# handmouse.net
KiCad netlist of a schematic drawn in Altium Designer
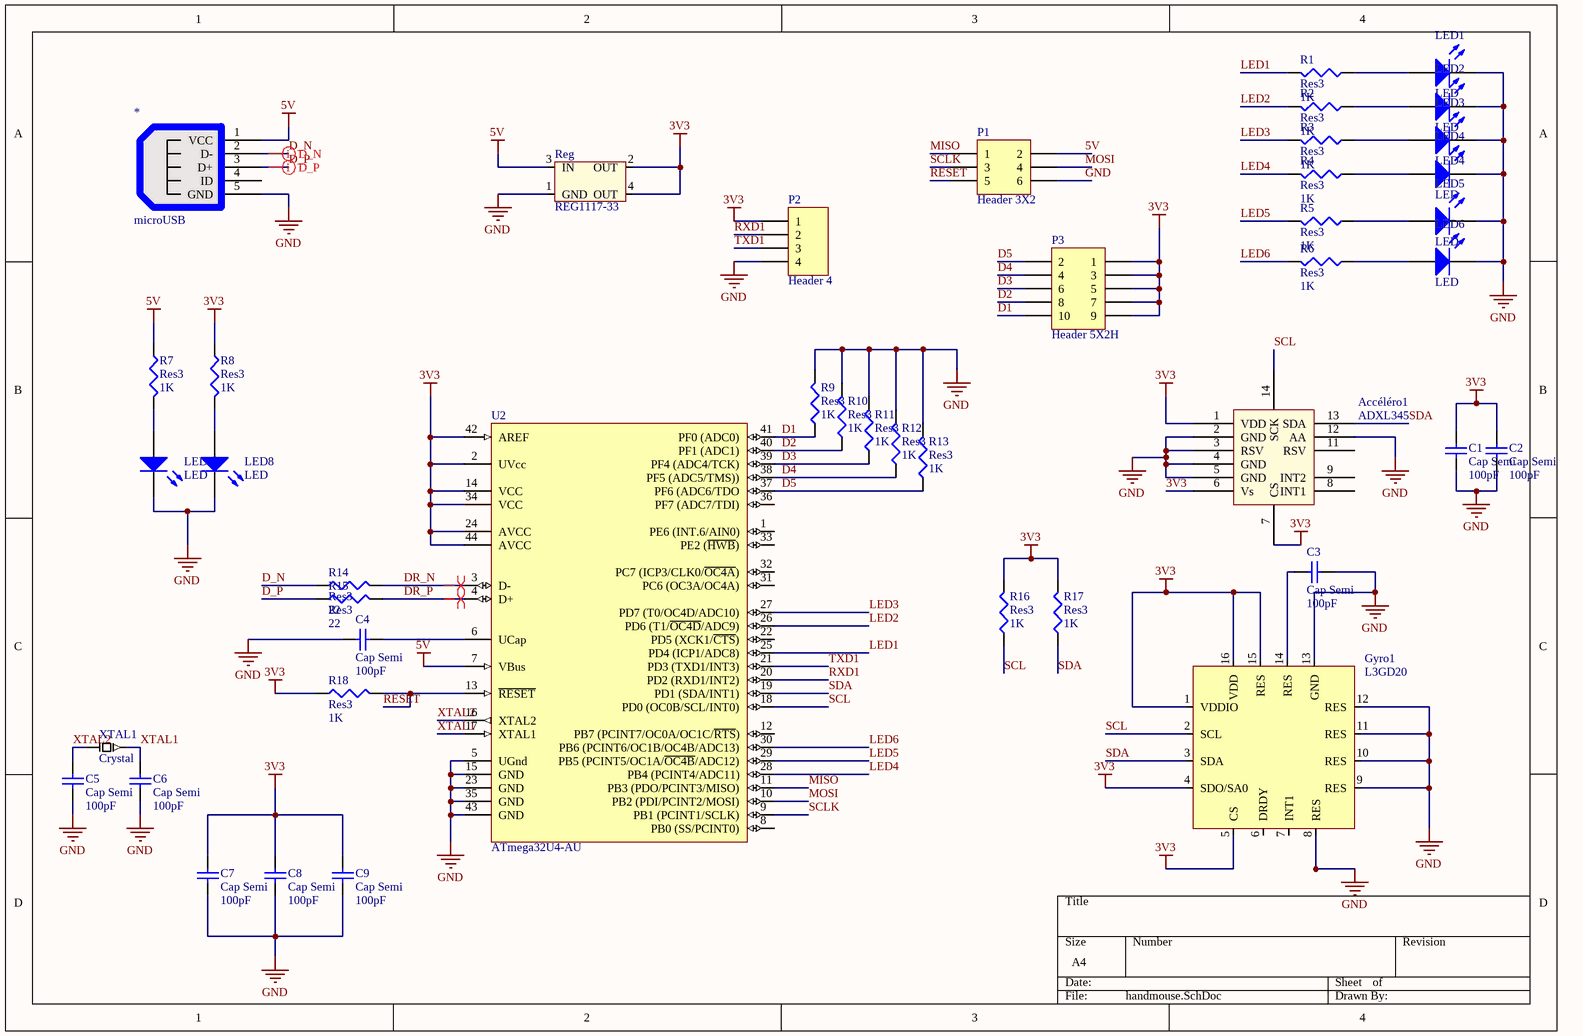
[diagram p0: handmouse.SchDoc]

(export (version "E")
  (design (tool "Eeschema 10.0.6"))
  (components
    (comp (ref "*") (value "microUSB") (footprint "microUSB") (libsource (lib "Schlib1") (part "microUSB")))
    (comp (ref "Accéléro1")
      (value "ADXL345")
      (footprint "PcbLib1:LGA-14")
      (libsource (lib "Schlib1") (part "ADXL345"))
    )
    (comp (ref "C1")
      (value "Cap Semi")
      (footprint "1608[0603]")
      (description "Capacitor (Semiconductor SIM Model)")
      (fields (field (name "ALTIUM_VALUE") "100pF") (field (name "PUBLISHER") "Altium Limited"))
      (libsource (lib "Miscellaneous Devices") (part "Cap Semi"))
    )
    (comp (ref "C2")
      (value "Cap Semi")
      (footprint "1608[0603]")
      (description "Capacitor (Semiconductor SIM Model)")
      (fields (field (name "ALTIUM_VALUE") "100pF") (field (name "PUBLISHER") "Altium Limited"))
      (libsource (lib "Miscellaneous Devices") (part "Cap Semi"))
    )
    (comp (ref "C3")
      (value "Cap Semi")
      (footprint "1608[0603]")
      (description "Capacitor (Semiconductor SIM Model)")
      (fields (field (name "ALTIUM_VALUE") "100pF") (field (name "PUBLISHER") "Altium Limited"))
      (libsource (lib "Miscellaneous Devices") (part "Cap Semi"))
    )
    (comp (ref "C4")
      (value "Cap Semi")
      (footprint "1608[0603]")
      (description "Capacitor (Semiconductor SIM Model)")
      (fields (field (name "ALTIUM_VALUE") "100pF") (field (name "PUBLISHER") "Altium Limited"))
      (libsource (lib "Miscellaneous Devices") (part "Cap Semi"))
    )
    (comp (ref "C5")
      (value "Cap Semi")
      (footprint "1608[0603]")
      (description "Capacitor (Semiconductor SIM Model)")
      (fields (field (name "ALTIUM_VALUE") "100pF") (field (name "PUBLISHER") "Altium Limited"))
      (libsource (lib "Miscellaneous Devices") (part "Cap Semi"))
    )
    (comp (ref "C6")
      (value "Cap Semi")
      (footprint "1608[0603]")
      (description "Capacitor (Semiconductor SIM Model)")
      (fields (field (name "ALTIUM_VALUE") "100pF") (field (name "PUBLISHER") "Altium Limited"))
      (libsource (lib "Miscellaneous Devices") (part "Cap Semi"))
    )
    (comp (ref "C7")
      (value "Cap Semi")
      (footprint "1608[0603]")
      (description "Capacitor (Semiconductor SIM Model)")
      (fields (field (name "ALTIUM_VALUE") "100pF") (field (name "PUBLISHER") "Altium Limited"))
      (libsource (lib "Miscellaneous Devices") (part "Cap Semi"))
    )
    (comp (ref "C8")
      (value "Cap Semi")
      (footprint "1608[0603]")
      (description "Capacitor (Semiconductor SIM Model)")
      (fields (field (name "ALTIUM_VALUE") "100pF") (field (name "PUBLISHER") "Altium Limited"))
      (libsource (lib "Miscellaneous Devices") (part "Cap Semi"))
    )
    (comp (ref "C9")
      (value "Cap Semi")
      (footprint "1608[0603]")
      (description "Capacitor (Semiconductor SIM Model)")
      (fields (field (name "ALTIUM_VALUE") "100pF") (field (name "PUBLISHER") "Altium Limited"))
      (libsource (lib "Miscellaneous Devices") (part "Cap Semi"))
    )
    (comp (ref "Gyro1")
      (value "L3GD20")
      (footprint "PcbLib1:QFN16")
      (libsource (lib "Schlib1") (part "L3GD20"))
    )
    (comp (ref "LED1") (value "LED") (footprint "LED 0603") (libsource (lib "Schlib1") (part "LED")))
    (comp (ref "LED2") (value "LED") (footprint "LED 0603") (libsource (lib "Schlib1") (part "LED")))
    (comp (ref "LED3") (value "LED4") (footprint "LED 0603") (libsource (lib "Schlib1") (part "LED")))
    (comp (ref "LED4") (value "LED") (footprint "LED 0603") (libsource (lib "Schlib1") (part "LED")))
    (comp (ref "LED5") (value "LED") (footprint "LED 0603") (libsource (lib "Schlib1") (part "LED")))
    (comp (ref "LED6") (value "LED") (footprint "LED 0603") (libsource (lib "Schlib1") (part "LED")))
    (comp (ref "LED7") (value "LED") (footprint "LED 0603") (libsource (lib "Schlib1") (part "LED")))
    (comp (ref "LED8") (value "LED") (footprint "LED 0603") (libsource (lib "Schlib1") (part "LED")))
    (comp (ref "P1")
      (value "Header 3X2")
      (footprint "HDR2X3")
      (description "Header, 3-Pin, Dual row")
      (fields (field (name "PUBLISHER") "Altium Limited"))
      (libsource (lib "Miscellaneous Connectors") (part "Header 3X2"))
    )
    (comp (ref "P2")
      (value "Header 4")
      (footprint "HDR1X4")
      (description "Header, 4-Pin")
      (fields (field (name "PUBLISHER") "Altium Limited"))
      (libsource (lib "Miscellaneous Connectors") (part "Header 4"))
    )
    (comp (ref "P3")
      (value "Header 5X2H")
      (footprint "HDR2X5H")
      (description "Header, 5-Pin, Dual row, Right Angle")
      (fields (field (name "PUBLISHER") "Altium Limited"))
      (libsource (lib "Miscellaneous Connectors") (part "Header 5X2H"))
    )
    (comp (ref "R1")
      (value "Res3")
      (footprint "J1-0603")
      (description "Resistor")
      (fields (field (name "ALTIUM_VALUE") "1K") (field (name "PUBLISHER") "Altium Limited"))
      (libsource (lib "Miscellaneous Devices") (part "Res3"))
    )
    (comp (ref "R2")
      (value "Res3")
      (footprint "J1-0603")
      (description "Resistor")
      (fields (field (name "ALTIUM_VALUE") "1K") (field (name "PUBLISHER") "Altium Limited"))
      (libsource (lib "Miscellaneous Devices") (part "Res3"))
    )
    (comp (ref "R3")
      (value "Res3")
      (footprint "J1-0603")
      (description "Resistor")
      (fields (field (name "ALTIUM_VALUE") "1K") (field (name "PUBLISHER") "Altium Limited"))
      (libsource (lib "Miscellaneous Devices") (part "Res3"))
    )
    (comp (ref "R4")
      (value "Res3")
      (footprint "J1-0603")
      (description "Resistor")
      (fields (field (name "ALTIUM_VALUE") "1K") (field (name "PUBLISHER") "Altium Limited"))
      (libsource (lib "Miscellaneous Devices") (part "Res3"))
    )
    (comp (ref "R5")
      (value "Res3")
      (footprint "J1-0603")
      (description "Resistor")
      (fields (field (name "ALTIUM_VALUE") "1K") (field (name "PUBLISHER") "Altium Limited"))
      (libsource (lib "Miscellaneous Devices") (part "Res3"))
    )
    (comp (ref "R6")
      (value "Res3")
      (footprint "J1-0603")
      (description "Resistor")
      (fields (field (name "ALTIUM_VALUE") "1K") (field (name "PUBLISHER") "Altium Limited"))
      (libsource (lib "Miscellaneous Devices") (part "Res3"))
    )
    (comp (ref "R7")
      (value "Res3")
      (footprint "J1-0603")
      (description "Resistor")
      (fields (field (name "ALTIUM_VALUE") "1K") (field (name "PUBLISHER") "Altium Limited"))
      (libsource (lib "Miscellaneous Devices") (part "Res3"))
    )
    (comp (ref "R8")
      (value "Res3")
      (footprint "J1-0603")
      (description "Resistor")
      (fields (field (name "ALTIUM_VALUE") "1K") (field (name "PUBLISHER") "Altium Limited"))
      (libsource (lib "Miscellaneous Devices") (part "Res3"))
    )
    (comp (ref "R9")
      (value "Res3")
      (footprint "J1-0603")
      (description "Resistor")
      (fields (field (name "ALTIUM_VALUE") "1K") (field (name "PUBLISHER") "Altium Limited"))
      (libsource (lib "Miscellaneous Devices") (part "Res3"))
    )
    (comp (ref "R10")
      (value "Res3")
      (footprint "J1-0603")
      (description "Resistor")
      (fields (field (name "ALTIUM_VALUE") "1K") (field (name "PUBLISHER") "Altium Limited"))
      (libsource (lib "Miscellaneous Devices") (part "Res3"))
    )
    (comp (ref "R11")
      (value "Res3")
      (footprint "J1-0603")
      (description "Resistor")
      (fields (field (name "ALTIUM_VALUE") "1K") (field (name "PUBLISHER") "Altium Limited"))
      (libsource (lib "Miscellaneous Devices") (part "Res3"))
    )
    (comp (ref "R12")
      (value "Res3")
      (footprint "J1-0603")
      (description "Resistor")
      (fields (field (name "ALTIUM_VALUE") "1K") (field (name "PUBLISHER") "Altium Limited"))
      (libsource (lib "Miscellaneous Devices") (part "Res3"))
    )
    (comp (ref "R13")
      (value "Res3")
      (footprint "J1-0603")
      (description "Resistor")
      (fields (field (name "ALTIUM_VALUE") "1K") (field (name "PUBLISHER") "Altium Limited"))
      (libsource (lib "Miscellaneous Devices") (part "Res3"))
    )
    (comp (ref "R14")
      (value "Res3")
      (footprint "J1-0603")
      (description "Resistor")
      (fields (field (name "ALTIUM_VALUE") "22") (field (name "PUBLISHER") "Altium Limited"))
      (libsource (lib "Miscellaneous Devices") (part "Res3"))
    )
    (comp (ref "R15")
      (value "Res3")
      (footprint "J1-0603")
      (description "Resistor")
      (fields (field (name "ALTIUM_VALUE") "22") (field (name "PUBLISHER") "Altium Limited"))
      (libsource (lib "Miscellaneous Devices") (part "Res3"))
    )
    (comp (ref "R16")
      (value "Res3")
      (footprint "J1-0603")
      (description "Resistor")
      (fields (field (name "ALTIUM_VALUE") "1K") (field (name "PUBLISHER") "Altium Limited"))
      (libsource (lib "Miscellaneous Devices") (part "Res3"))
    )
    (comp (ref "R17")
      (value "Res3")
      (footprint "J1-0603")
      (description "Resistor")
      (fields (field (name "ALTIUM_VALUE") "1K") (field (name "PUBLISHER") "Altium Limited"))
      (libsource (lib "Miscellaneous Devices") (part "Res3"))
    )
    (comp (ref "R18")
      (value "Res3")
      (footprint "J1-0603")
      (description "Resistor")
      (fields (field (name "ALTIUM_VALUE") "1K") (field (name "PUBLISHER") "Altium Limited"))
      (libsource (lib "Miscellaneous Devices") (part "Res3"))
    )
    (comp (ref "Reg")
      (value "REG1117-33")
      (footprint "SOT-223")
      (libsource (lib "Schlib1") (part "REG1117-33"))
    )
    (comp (ref "U2")
      (value "ATmega32U4-AU")
      (footprint "44ML_N")
      (fields (field (name "PUBLISHER") "Altium Limited"))
      (libsource (lib "Atmel Microcontroller 8-Bit megaAVR") (part "ATmega32U4-AU"))
    )
    (comp (ref "XTAL1") (value "Crystal") (footprint "HC49-CMS") (libsource (lib "Schlib1") (part "Crystal")))
  )
  (nets
    (net (code "1") (name "/D1") (class "Default")
      (node (ref "P3") (pin "10") (pinfunction "10_10") (pintype "passive"))
      (node (ref "R9") (pin "1") (pinfunction "1_1") (pintype "passive"))
      (node (ref "U2") (pin "41") (pinfunction "PF0_(ADC0)_41") (pintype "bidirectional"))
    )
    (net (code "2") (name "/D2") (class "Default")
      (node (ref "P3") (pin "8") (pinfunction "8_8") (pintype "passive"))
      (node (ref "R10") (pin "1") (pinfunction "1_1") (pintype "passive"))
      (node (ref "U2") (pin "40") (pinfunction "PF1_(ADC1)_40") (pintype "bidirectional"))
    )
    (net (code "3") (name "/D3") (class "Default")
      (node (ref "P3") (pin "6") (pinfunction "6_6") (pintype "passive"))
      (node (ref "R11") (pin "1") (pinfunction "1_1") (pintype "passive"))
      (node (ref "U2") (pin "39") (pinfunction "PF4_(ADC4/TCK)_39") (pintype "bidirectional"))
    )
    (net (code "4") (name "/D4") (class "Default")
      (node (ref "P3") (pin "4") (pinfunction "4_4") (pintype "passive"))
      (node (ref "R12") (pin "1") (pinfunction "1_1") (pintype "passive"))
      (node (ref "U2") (pin "38") (pinfunction "PF5_(ADC5/TMS))_38") (pintype "bidirectional"))
    )
    (net (code "5") (name "/D5") (class "Default")
      (node (ref "P3") (pin "2") (pinfunction "2_2") (pintype "passive"))
      (node (ref "R13") (pin "1") (pinfunction "1_1") (pintype "passive"))
      (node (ref "U2") (pin "37") (pinfunction "PF6_(ADC6/TDO_37") (pintype "bidirectional"))
    )
    (net (code "6") (name "/DR_N") (class "Default")
      (node (ref "R14") (pin "2") (pinfunction "2_2") (pintype "passive"))
      (node (ref "U2") (pin "3") (pinfunction "D-_3") (pintype "bidirectional"))
    )
    (net (code "7") (name "/DR_P") (class "Default")
      (node (ref "R15") (pin "2") (pinfunction "2_2") (pintype "passive"))
      (node (ref "U2") (pin "4") (pinfunction "D+_4") (pintype "bidirectional"))
    )
    (net (code "8") (name "/D_N") (class "Default")
      (node (ref "*") (pin "2") (pinfunction "D-_2") (pintype "passive"))
      (node (ref "R14") (pin "1") (pinfunction "1_1") (pintype "passive"))
    )
    (net (code "9") (name "/D_P") (class "Default")
      (node (ref "*") (pin "3") (pinfunction "D+_3") (pintype "passive"))
      (node (ref "R15") (pin "1") (pinfunction "1_1") (pintype "passive"))
    )
    (net (code "10") (name "/LED1") (class "Default")
      (node (ref "R1") (pin "2") (pinfunction "2_2") (pintype "passive"))
      (node (ref "U2") (pin "25") (pinfunction "PD4_(ICP1/ADC8)_25") (pintype "bidirectional"))
    )
    (net (code "11") (name "/LED2") (class "Default")
      (node (ref "R2") (pin "2") (pinfunction "2_2") (pintype "passive"))
      (node (ref "U2") (pin "26") (pinfunction "PD6_(T1/~{OC4D}/ADC9)_26") (pintype "bidirectional"))
    )
    (net (code "12") (name "/LED3") (class "Default")
      (node (ref "R3") (pin "2") (pinfunction "2_2") (pintype "passive"))
      (node (ref "U2") (pin "27") (pinfunction "PD7_(T0/OC4D/ADC10)_27") (pintype "bidirectional"))
    )
    (net (code "13") (name "/LED4") (class "Default")
      (node (ref "R4") (pin "2") (pinfunction "2_2") (pintype "passive"))
      (node (ref "U2") (pin "28") (pinfunction "PB4_(PCINT4/ADC11)_28") (pintype "bidirectional"))
    )
    (net (code "14") (name "/LED5") (class "Default")
      (node (ref "R5") (pin "2") (pinfunction "2_2") (pintype "passive"))
      (node (ref "U2") (pin "29") (pinfunction "PB5_(PCINT5/OC1A/~{OC4B}/ADC12)_29") (pintype "bidirectional"))
    )
    (net (code "15") (name "/LED6") (class "Default")
      (node (ref "R6") (pin "2") (pinfunction "2_2") (pintype "passive"))
      (node (ref "U2") (pin "30") (pinfunction "PB6_(PCINT6/OC1B/OC4B/ADC13)_30") (pintype "bidirectional"))
    )
    (net (code "16") (name "/MISO") (class "Default")
      (node (ref "P1") (pin "1") (pinfunction "1_1") (pintype "passive"))
      (node (ref "U2") (pin "11") (pinfunction "PB3_(PDO/PCINT3/MISO)_11") (pintype "bidirectional"))
    )
    (net (code "17") (name "/MOSI") (class "Default")
      (node (ref "P1") (pin "4") (pinfunction "4_4") (pintype "passive"))
      (node (ref "U2") (pin "10") (pinfunction "PB2_(PDI/PCINT2/MOSI)_10") (pintype "bidirectional"))
    )
    (net (code "18") (name "/RESET") (class "Default")
      (node (ref "P1") (pin "5") (pinfunction "5_5") (pintype "passive"))
      (node (ref "R18") (pin "2") (pinfunction "2_2") (pintype "passive"))
      (node (ref "U2") (pin "13") (pinfunction "~{RESET}_13") (pintype "input"))
    )
    (net (code "19") (name "/RXD1") (class "Default")
      (node (ref "P2") (pin "2") (pinfunction "2_2") (pintype "passive"))
      (node (ref "U2") (pin "20") (pinfunction "PD2_(RXD1/INT2)_20") (pintype "bidirectional"))
    )
    (net (code "20") (name "/SCL") (class "Default")
      (node (ref "Accéléro1") (pin "14") (pinfunction "SCK_14") (pintype "passive"))
      (node (ref "Gyro1") (pin "2") (pinfunction "SCL_2") (pintype "passive"))
      (node (ref "R16") (pin "1") (pinfunction "1_1") (pintype "passive"))
      (node (ref "U2") (pin "18") (pinfunction "PD0_(OC0B/SCL/INT0)_18") (pintype "bidirectional"))
    )
    (net (code "21") (name "/SCLK") (class "Default")
      (node (ref "P1") (pin "3") (pinfunction "3_3") (pintype "passive"))
      (node (ref "U2") (pin "9") (pinfunction "PB1_(PCINT1/SCLK)_9") (pintype "bidirectional"))
    )
    (net (code "22") (name "/SDA") (class "Default")
      (node (ref "Accéléro1") (pin "13") (pinfunction "SDA_13") (pintype "passive"))
      (node (ref "Gyro1") (pin "3") (pinfunction "SDA_3") (pintype "passive"))
      (node (ref "R17") (pin "1") (pinfunction "1_1") (pintype "passive"))
      (node (ref "U2") (pin "19") (pinfunction "PD1_(SDA/INT1)_19") (pintype "bidirectional"))
    )
    (net (code "23") (name "/TXD1") (class "Default")
      (node (ref "P2") (pin "3") (pinfunction "3_3") (pintype "passive"))
      (node (ref "U2") (pin "21") (pinfunction "PD3_(TXD1/INT3)_21") (pintype "bidirectional"))
    )
    (net (code "24") (name "/XTAL1") (class "Default")
      (node (ref "C6") (pin "2") (pinfunction "2_2") (pintype "passive"))
      (node (ref "U2") (pin "17") (pinfunction "XTAL1_17") (pintype "input"))
      (node (ref "XTAL1") (pin "2") (pinfunction "2_2") (pintype "output"))
    )
    (net (code "25") (name "/XTAL2") (class "Default")
      (node (ref "C5") (pin "2") (pinfunction "2_2") (pintype "passive"))
      (node (ref "U2") (pin "16") (pinfunction "XTAL2_16") (pintype "output"))
      (node (ref "XTAL1") (pin "1") (pinfunction "1_1") (pintype "passive"))
    )
    (net (code "26") (name "3V3") (class "Default")
      (node (ref "Accéléro1") (pin "1") (pinfunction "VDD_1") (pintype "power_in"))
      (node (ref "Accéléro1") (pin "6") (pinfunction "Vs_6") (pintype "passive"))
      (node (ref "Accéléro1") (pin "7") (pinfunction "CS_7") (pintype "passive"))
      (node (ref "C1") (pin "2") (pinfunction "2_2") (pintype "passive"))
      (node (ref "C2") (pin "2") (pinfunction "2_2") (pintype "passive"))
      (node (ref "C7") (pin "2") (pinfunction "2_2") (pintype "passive"))
      (node (ref "C8") (pin "2") (pinfunction "2_2") (pintype "passive"))
      (node (ref "C9") (pin "2") (pinfunction "2_2") (pintype "passive"))
      (node (ref "Gyro1") (pin "1") (pinfunction "VDDIO_1") (pintype "power_in"))
      (node (ref "Gyro1") (pin "15") (pinfunction "RES_15") (pintype "passive"))
      (node (ref "Gyro1") (pin "16") (pinfunction "VDD_16") (pintype "power_in"))
      (node (ref "Gyro1") (pin "4") (pinfunction "SDO/SA0_4") (pintype "passive"))
      (node (ref "Gyro1") (pin "5") (pinfunction "CS_5") (pintype "passive"))
      (node (ref "P2") (pin "1") (pinfunction "1_1") (pintype "passive"))
      (node (ref "P3") (pin "1") (pinfunction "1_1") (pintype "passive"))
      (node (ref "P3") (pin "3") (pinfunction "3_3") (pintype "passive"))
      (node (ref "P3") (pin "5") (pinfunction "5_5") (pintype "passive"))
      (node (ref "P3") (pin "7") (pinfunction "7_7") (pintype "passive"))
      (node (ref "P3") (pin "9") (pinfunction "9_9") (pintype "passive"))
      (node (ref "R16") (pin "2") (pinfunction "2_2") (pintype "passive"))
      (node (ref "R17") (pin "2") (pinfunction "2_2") (pintype "passive"))
      (node (ref "R18") (pin "1") (pinfunction "1_1") (pintype "passive"))
      (node (ref "R8") (pin "1") (pinfunction "1_1") (pintype "passive"))
      (node (ref "Reg") (pin "2") (pinfunction "OUT_2") (pintype "passive"))
      (node (ref "Reg") (pin "4") (pinfunction "OUT_4") (pintype "passive"))
      (node (ref "U2") (pin "14") (pinfunction "VCC_14") (pintype "power_in"))
      (node (ref "U2") (pin "2") (pinfunction "UVcc_2") (pintype "power_in"))
      (node (ref "U2") (pin "24") (pinfunction "AVCC_24") (pintype "power_in"))
      (node (ref "U2") (pin "34") (pinfunction "VCC_34") (pintype "power_in"))
      (node (ref "U2") (pin "42") (pinfunction "AREF_42") (pintype "input"))
      (node (ref "U2") (pin "44") (pinfunction "AVCC_44") (pintype "power_in"))
    )
    (net (code "27") (name "5V") (class "Default")
      (node (ref "*") (pin "1") (pinfunction "VCC_1") (pintype "power_in"))
      (node (ref "P1") (pin "2") (pinfunction "2_2") (pintype "passive"))
      (node (ref "R7") (pin "1") (pinfunction "1_1") (pintype "passive"))
      (node (ref "Reg") (pin "3") (pinfunction "IN_3") (pintype "passive"))
      (node (ref "U2") (pin "7") (pinfunction "VBus_7") (pintype "input"))
    )
    (net (code "28") (name "GND") (class "Default")
      (node (ref "*") (pin "5") (pinfunction "GND_5") (pintype "passive"))
      (node (ref "Accéléro1") (pin "12") (pinfunction "AA_12") (pintype "passive"))
      (node (ref "Accéléro1") (pin "2") (pinfunction "GND_2") (pintype "power_in"))
      (node (ref "Accéléro1") (pin "3") (pinfunction "RSV_3") (pintype "passive"))
      (node (ref "Accéléro1") (pin "4") (pinfunction "GND_4") (pintype "power_in"))
      (node (ref "Accéléro1") (pin "5") (pinfunction "GND_5") (pintype "power_in"))
      (node (ref "C1") (pin "1") (pinfunction "1_1") (pintype "passive"))
      (node (ref "C2") (pin "1") (pinfunction "1_1") (pintype "passive"))
      (node (ref "C3") (pin "1") (pinfunction "1_1") (pintype "passive"))
      (node (ref "C4") (pin "2") (pinfunction "2_2") (pintype "passive"))
      (node (ref "C5") (pin "1") (pinfunction "1_1") (pintype "passive"))
      (node (ref "C6") (pin "1") (pinfunction "1_1") (pintype "passive"))
      (node (ref "C7") (pin "1") (pinfunction "1_1") (pintype "passive"))
      (node (ref "C8") (pin "1") (pinfunction "1_1") (pintype "passive"))
      (node (ref "C9") (pin "1") (pinfunction "1_1") (pintype "passive"))
      (node (ref "Gyro1") (pin "10") (pinfunction "RES_10") (pintype "passive"))
      (node (ref "Gyro1") (pin "11") (pinfunction "RES_11") (pintype "passive"))
      (node (ref "Gyro1") (pin "12") (pinfunction "RES_12") (pintype "passive"))
      (node (ref "Gyro1") (pin "13") (pinfunction "GND_13") (pintype "passive"))
      (node (ref "Gyro1") (pin "8") (pinfunction "RES_8") (pintype "passive"))
      (node (ref "Gyro1") (pin "9") (pinfunction "RES_9") (pintype "passive"))
      (node (ref "LED1") (pin "2") (pinfunction "K_2") (pintype "passive"))
      (node (ref "LED2") (pin "2") (pinfunction "K_2") (pintype "passive"))
      (node (ref "LED3") (pin "2") (pinfunction "K_2") (pintype "passive"))
      (node (ref "LED4") (pin "2") (pinfunction "K_2") (pintype "passive"))
      (node (ref "LED5") (pin "2") (pinfunction "K_2") (pintype "passive"))
      (node (ref "LED6") (pin "2") (pinfunction "K_2") (pintype "passive"))
      (node (ref "LED7") (pin "2") (pinfunction "K_2") (pintype "passive"))
      (node (ref "LED8") (pin "2") (pinfunction "K_2") (pintype "passive"))
      (node (ref "P1") (pin "6") (pinfunction "6_6") (pintype "passive"))
      (node (ref "P2") (pin "4") (pinfunction "4_4") (pintype "passive"))
      (node (ref "R10") (pin "2") (pinfunction "2_2") (pintype "passive"))
      (node (ref "R11") (pin "2") (pinfunction "2_2") (pintype "passive"))
      (node (ref "R12") (pin "2") (pinfunction "2_2") (pintype "passive"))
      (node (ref "R13") (pin "2") (pinfunction "2_2") (pintype "passive"))
      (node (ref "R9") (pin "2") (pinfunction "2_2") (pintype "passive"))
      (node (ref "Reg") (pin "1") (pinfunction "GND_1") (pintype "passive"))
      (node (ref "U2") (pin "15") (pinfunction "GND_15") (pintype "power_in"))
      (node (ref "U2") (pin "23") (pinfunction "GND_23") (pintype "power_in"))
      (node (ref "U2") (pin "35") (pinfunction "GND_35") (pintype "power_in"))
      (node (ref "U2") (pin "43") (pinfunction "GND_43") (pintype "power_in"))
      (node (ref "U2") (pin "5") (pinfunction "UGnd_5") (pintype "power_in"))
    )
    (net (code "29") (name "Net-(C3-Pad2)") (class "Default")
      (node (ref "C3") (pin "2") (pinfunction "2_2") (pintype "passive"))
      (node (ref "Gyro1") (pin "14") (pinfunction "RES_14") (pintype "passive"))
    )
    (net (code "30") (name "Net-(LED1-A)") (class "Default")
      (node (ref "LED1") (pin "1") (pinfunction "A_1") (pintype "passive"))
      (node (ref "R1") (pin "1") (pinfunction "1_1") (pintype "passive"))
    )
    (net (code "31") (name "Net-(LED2-A)") (class "Default")
      (node (ref "LED2") (pin "1") (pinfunction "A_1") (pintype "passive"))
      (node (ref "R2") (pin "1") (pinfunction "1_1") (pintype "passive"))
    )
    (net (code "32") (name "Net-(LED3-A)") (class "Default")
      (node (ref "LED3") (pin "1") (pinfunction "A_1") (pintype "passive"))
      (node (ref "R3") (pin "1") (pinfunction "1_1") (pintype "passive"))
    )
    (net (code "33") (name "Net-(LED4-A)") (class "Default")
      (node (ref "LED4") (pin "1") (pinfunction "A_1") (pintype "passive"))
      (node (ref "R4") (pin "1") (pinfunction "1_1") (pintype "passive"))
    )
    (net (code "34") (name "Net-(LED5-A)") (class "Default")
      (node (ref "LED5") (pin "1") (pinfunction "A_1") (pintype "passive"))
      (node (ref "R5") (pin "1") (pinfunction "1_1") (pintype "passive"))
    )
    (net (code "35") (name "Net-(LED6-A)") (class "Default")
      (node (ref "LED6") (pin "1") (pinfunction "A_1") (pintype "passive"))
      (node (ref "R6") (pin "1") (pinfunction "1_1") (pintype "passive"))
    )
    (net (code "36") (name "Net-(LED7-A)") (class "Default")
      (node (ref "LED7") (pin "1") (pinfunction "A_1") (pintype "passive"))
      (node (ref "R7") (pin "2") (pinfunction "2_2") (pintype "passive"))
    )
    (net (code "37") (name "Net-(LED8-A)") (class "Default")
      (node (ref "LED8") (pin "1") (pinfunction "A_1") (pintype "passive"))
      (node (ref "R8") (pin "2") (pinfunction "2_2") (pintype "passive"))
    )
    (net (code "38") (name "Net-(U2-UCap)") (class "Default")
      (node (ref "C4") (pin "1") (pinfunction "1_1") (pintype "passive"))
      (node (ref "U2") (pin "6") (pinfunction "UCap_6") (pintype "passive"))
    )
    (net (code "39") (name "unconnected-(*-ID-Pad4)") (class "Default")
      (node (ref "*") (pin "4") (pinfunction "ID_4") (pintype "passive"))
    )
    (net (code "40") (name "unconnected-(Accéléro1-INT1-Pad8)") (class "Default")
      (node (ref "Accéléro1") (pin "8") (pinfunction "INT1_8") (pintype "passive"))
    )
    (net (code "41") (name "unconnected-(Accéléro1-INT2-Pad9)") (class "Default")
      (node (ref "Accéléro1") (pin "9") (pinfunction "INT2_9") (pintype "passive"))
    )
    (net (code "42") (name "unconnected-(Accéléro1-NC-Pad10)") (class "Default")
      (node (ref "Accéléro1") (pin "10") (pinfunction "NC_10") (pintype "passive"))
    )
    (net (code "43") (name "unconnected-(Accéléro1-RSV-Pad11)") (class "Default")
      (node (ref "Accéléro1") (pin "11") (pinfunction "RSV_11") (pintype "passive"))
    )
    (net (code "44") (name "unconnected-(Gyro1-DRDY-Pad6)") (class "Default")
      (node (ref "Gyro1") (pin "6") (pinfunction "DRDY_6") (pintype "passive"))
    )
    (net (code "45") (name "unconnected-(Gyro1-INT1-Pad7)") (class "Default")
      (node (ref "Gyro1") (pin "7") (pinfunction "INT1_7") (pintype "passive"))
    )
    (net (code "46") (name "unconnected-(U2-PB0_(SS{slash}PCINT0)-Pad8)") (class "Default")
      (node (ref "U2") (pin "8") (pinfunction "PB0_(SS/PCINT0)_8") (pintype "bidirectional"))
    )
    (net (code "47") (name "unconnected-(U2-PB7_(PCINT7{slash}OC0A{slash}OC1C{slash}~{RTS})-Pad12)") (class "Default")
      (node (ref "U2") (pin "12") (pinfunction "PB7_(PCINT7/OC0A/OC1C/~{RTS})_12") (pintype "bidirectional"))
    )
    (net (code "48") (name "unconnected-(U2-PC6_(OC3A{slash}OC4A)-Pad31)") (class "Default")
      (node (ref "U2") (pin "31") (pinfunction "PC6_(OC3A/OC4A)_31") (pintype "bidirectional"))
    )
    (net (code "49") (name "unconnected-(U2-PC7_(ICP3{slash}CLK0{slash}~{OC4A})-Pad32)") (class "Default")
      (node (ref "U2") (pin "32") (pinfunction "PC7_(ICP3/CLK0/~{OC4A})_32") (pintype "bidirectional"))
    )
    (net (code "50") (name "unconnected-(U2-PD5_(XCK1{slash}~{CTS})-Pad22)") (class "Default")
      (node (ref "U2") (pin "22") (pinfunction "PD5_(XCK1/~{CTS})_22") (pintype "bidirectional"))
    )
    (net (code "51") (name "unconnected-(U2-PE2_(~{HWB})-Pad33)") (class "Default")
      (node (ref "U2") (pin "33") (pinfunction "PE2_(~{HWB})_33") (pintype "bidirectional"))
    )
    (net (code "52") (name "unconnected-(U2-PE6_(INT.6{slash}AIN0)-Pad1)") (class "Default")
      (node (ref "U2") (pin "1") (pinfunction "PE6_(INT.6/AIN0)_1") (pintype "bidirectional"))
    )
    (net (code "53") (name "unconnected-(U2-PF7_(ADC7{slash}TDI)-Pad36)") (class "Default")
      (node (ref "U2") (pin "36") (pinfunction "PF7_(ADC7/TDI)_36") (pintype "bidirectional"))
    )
  )
)
